# Barometer.net
KiCad netlist of a schematic drawn in Altium Designer
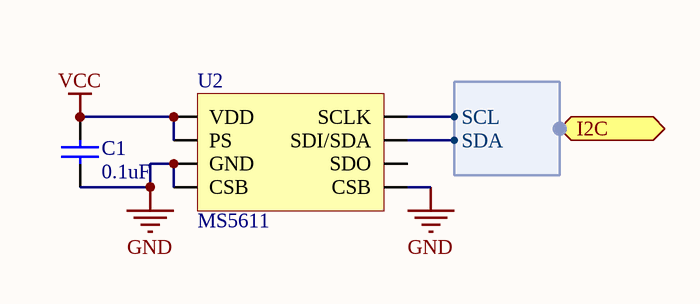
[diagram p0: Barometer.SchDoc]

(export (version "E")
  (design (tool "Eeschema 10.0.6"))
  (components
    (comp (ref "C1")
      (value "0.1uF")
      (footprint "C0402[1005X55]")
      (description "0.1uF 6.3V 10% 0402 (1005 Metric)")
      (fields (field (name "TOLERANCE") "10%") (field (name "PARTNUMBER") "GRM155R70J104KA01D"))
      (libsource (lib "Capacitors") (part "CAP_0.1uF_6.3V_0402_10%"))
    )
    (comp (ref "U2") (value "MS5611") (footprint "MS5611") (libsource (lib "Components") (part "MS5611")))
  )
  (nets
    (net (code "2") (name "/SCL") (class "Default")
      (node (ref "U2") (pin "8") (pinfunction "SCLK_8") (pintype "passive"))
    )
    (net (code "3") (name "/SDA") (class "Default")
      (node (ref "U2") (pin "7") (pinfunction "SDI/SDA_7") (pintype "passive"))
    )
    (net (code "5") (name "GND") (class "Default")
      (node (ref "C1") (pin "1") (pinfunction "1_1") (pintype "passive"))
      (node (ref "U2") (pin "3") (pinfunction "GND_3") (pintype "passive"))
      (node (ref "U2") (pin "4") (pinfunction "CSB_4") (pintype "passive"))
      (node (ref "U2") (pin "5") (pinfunction "CSB_5") (pintype "passive"))
    )
    (net (code "6") (name "VCC") (class "Default")
      (node (ref "C1") (pin "2") (pinfunction "2_2") (pintype "passive"))
      (node (ref "U2") (pin "1") (pinfunction "VDD_1") (pintype "passive"))
      (node (ref "U2") (pin "2") (pinfunction "PS_2") (pintype "passive"))
    )
    (net (code "7") (name "unconnected-(U2-SDO-Pad6)") (class "Default")
      (node (ref "U2") (pin "6") (pinfunction "SDO_6") (pintype "passive"))
    )
  )
)
